# Arduino_Nano_33_IOT_Header_Schematic.net
KiCad netlist of a schematic drawn in EAGLE
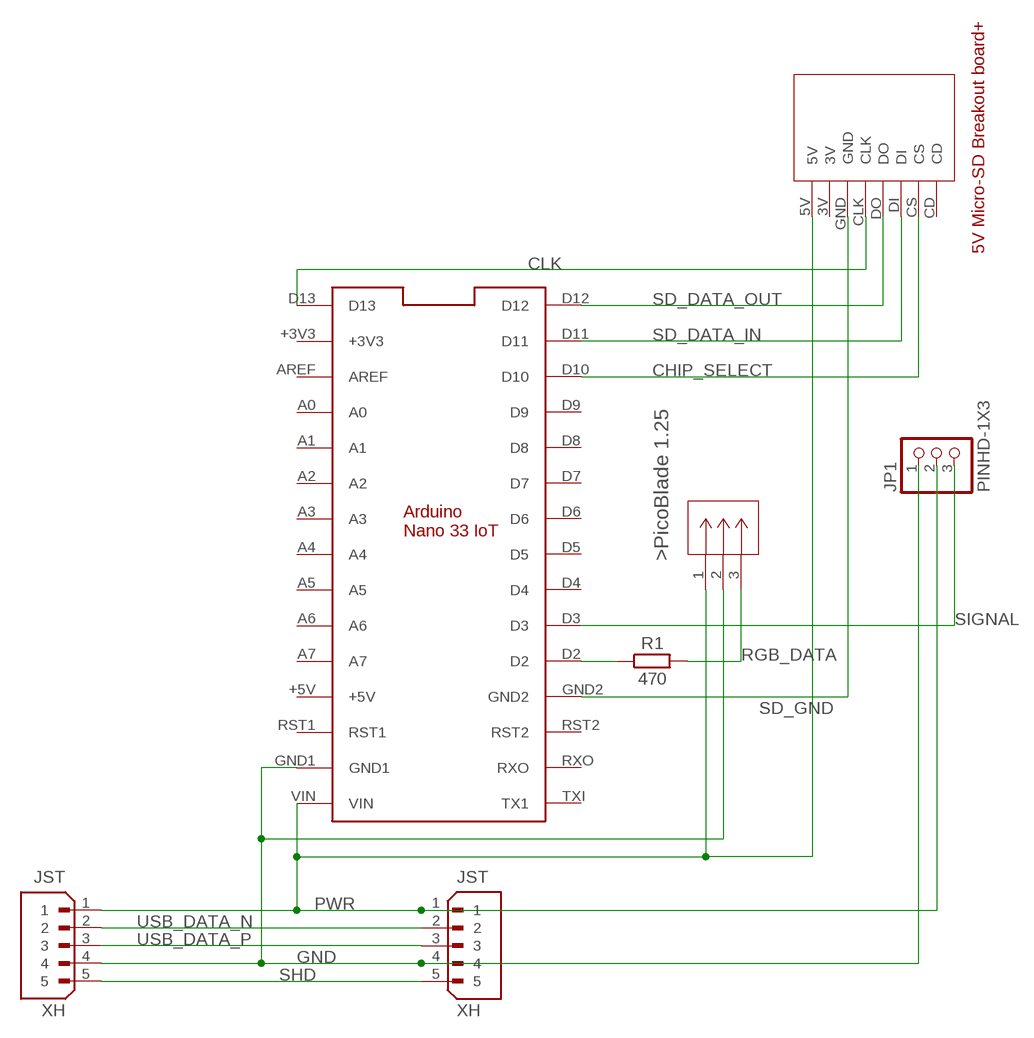
[diagram p0: schematic, sheet 1]

(export (version "E")
  (design (tool "Eeschema 10.0.6"))
  (components
    (comp (ref "HEADER2PCB")
      (value "B5B-XH-A")
      (footprint "eagle-import:JST_B5B-XH-A")
      (fields (field (name "MANUFACTURER") "JST") (field (name "MPN") "3"))
      (libsource (lib "eagle-import") (part "B5B-XH-A"))
    )
    (comp (ref "J1")
      (value "PICOBLADE_1.25_3-PINCONN03_530470310_MOL")
      (footprint "eagle-import:PICOBLADE_1.25_3-PIN")
      (fields
        (field (name "MANUFACTURER") "Molex")
        (field (name "MANUFACTURER_PART_NUMBER") "530470310")
        (field (name "COPYRIGHT") "Copyright (C) 2025 Ultra Librarian. All rights reserved.")
      )
      (libsource (lib "eagle-import") (part "PICOBLADE_1.25_3-PINCONN03_530470310_MOL"))
    )
    (comp (ref "JP1")
      (value "PINHD-1X3")
      (footprint "eagle-import:1X03")
      (libsource (lib "eagle-import") (part "PINHD-1X3"))
    )
    (comp (ref "MICROSD_HEADER")
      (value "MICROSDCARDBREAKOUTBOARD+HEADER")
      (footprint "eagle-import:5V_MICRO-SD_BREAKOUT+_HEADERS")
      (libsource (lib "eagle-import") (part "MICROSDCARDBREAKOUTBOARD+HEADER"))
    )
    (comp (ref "R1")
      (value "470")
      (footprint "eagle-import:RESAD724W46L381D178B")
      (libsource (lib "eagle-import") (part "RESISTOR_AXIAL-7.2MM-PITCH_"))
    )
    (comp (ref "U$2")
      (value "ARDUINO_NANOHEADERS")
      (footprint "eagle-import:NANO_33_IOT_HEADER")
      (libsource (lib "eagle-import") (part "ARDUINO_NANOHEADERS"))
    )
    (comp (ref "USBCONNECT")
      (value "B5B-XH-A")
      (footprint "eagle-import:JST_B5B-XH-A")
      (fields (field (name "MANUFACTURER") "JST") (field (name "MPN") "3"))
      (libsource (lib "eagle-import") (part "B5B-XH-A"))
    )
  )
  (nets
    (net (code "1") (name "/CHIP_SELECT") (class "Default")
      (node (ref "MICROSD_HEADER") (pin "CS") (pinfunction "CS_CS") (pintype "input"))
      (node (ref "U$2") (pin "D10") (pinfunction "D10_D10") (pintype "bidirectional"))
    )
    (net (code "2") (name "/CLK") (class "Default")
      (node (ref "MICROSD_HEADER") (pin "CLK") (pinfunction "CLK_CLK") (pintype "input"))
      (node (ref "U$2") (pin "D13") (pinfunction "D13_D13") (pintype "bidirectional"))
    )
    (net (code "3") (name "/GND") (class "Default")
      (node (ref "HEADER2PCB") (pin "4") (pinfunction "4_4") (pintype "passive"))
      (node (ref "J1") (pin "2") (pinfunction "2_2") (pintype "passive"))
      (node (ref "JP1") (pin "1") (pinfunction "1_1") (pintype "passive"))
      (node (ref "U$2") (pin "GND1") (pinfunction "GND1_GND1") (pintype "bidirectional"))
      (node (ref "USBCONNECT") (pin "4") (pinfunction "4_4") (pintype "passive"))
    )
    (net (code "4") (name "/PWR") (class "Default")
      (node (ref "HEADER2PCB") (pin "1") (pinfunction "1_1") (pintype "passive"))
      (node (ref "J1") (pin "1") (pinfunction "1_1") (pintype "passive"))
      (node (ref "JP1") (pin "2") (pinfunction "2_2") (pintype "passive"))
      (node (ref "MICROSD_HEADER") (pin "5V") (pinfunction "5V_5V") (pintype "input"))
      (node (ref "U$2") (pin "VIN") (pinfunction "VIN_VIN") (pintype "output"))
      (node (ref "USBCONNECT") (pin "1") (pinfunction "1_1") (pintype "passive"))
    )
    (net (code "5") (name "/RGB_DATA") (class "Default")
      (node (ref "J1") (pin "3") (pinfunction "3_3") (pintype "passive"))
      (node (ref "R1") (pin "2") (pinfunction "2_2") (pintype "passive"))
    )
    (net (code "6") (name "/SD_DATA_IN") (class "Default")
      (node (ref "MICROSD_HEADER") (pin "DI") (pinfunction "DI_DI") (pintype "input"))
      (node (ref "U$2") (pin "D11") (pinfunction "D11_D11") (pintype "bidirectional"))
    )
    (net (code "7") (name "/SD_DATA_OUT") (class "Default")
      (node (ref "MICROSD_HEADER") (pin "DO") (pinfunction "DO_DO") (pintype "output"))
      (node (ref "U$2") (pin "D12") (pinfunction "D12_D12") (pintype "bidirectional"))
    )
    (net (code "8") (name "/SD_GND") (class "Default")
      (node (ref "MICROSD_HEADER") (pin "GND") (pinfunction "GND_GND") (pintype "bidirectional"))
      (node (ref "U$2") (pin "GND2") (pinfunction "GND2_GND2") (pintype "bidirectional"))
    )
    (net (code "9") (name "/SHD") (class "Default")
      (node (ref "HEADER2PCB") (pin "5") (pinfunction "5_5") (pintype "passive"))
      (node (ref "USBCONNECT") (pin "5") (pinfunction "5_5") (pintype "passive"))
    )
    (net (code "10") (name "/SIGNAL") (class "Default")
      (node (ref "JP1") (pin "3") (pinfunction "3_3") (pintype "passive"))
      (node (ref "U$2") (pin "D3") (pinfunction "D3_D3") (pintype "bidirectional"))
    )
    (net (code "11") (name "/USB_DATA_N") (class "Default")
      (node (ref "HEADER2PCB") (pin "2") (pinfunction "2_2") (pintype "passive"))
      (node (ref "USBCONNECT") (pin "2") (pinfunction "2_2") (pintype "passive"))
    )
    (net (code "12") (name "/USB_DATA_P") (class "Default")
      (node (ref "HEADER2PCB") (pin "3") (pinfunction "3_3") (pintype "passive"))
      (node (ref "USBCONNECT") (pin "3") (pinfunction "3_3") (pintype "passive"))
    )
    (net (code "13") (name "Net-(R1-Pad1)") (class "Default")
      (node (ref "R1") (pin "1") (pinfunction "1_1") (pintype "passive"))
      (node (ref "U$2") (pin "D2") (pinfunction "D2_D2") (pintype "bidirectional"))
    )
    (net (code "14") (name "unconnected-(MICROSD_HEADER-Pad3V)") (class "Default")
      (node (ref "MICROSD_HEADER") (pin "3V") (pinfunction "3V_3V") (pintype "bidirectional"))
    )
    (net (code "15") (name "unconnected-(MICROSD_HEADER-PadCD)") (class "Default")
      (node (ref "MICROSD_HEADER") (pin "CD") (pinfunction "CD_CD") (pintype "bidirectional"))
    )
    (net (code "16") (name "unconnected-(U$2-Pad+3V3)") (class "Default")
      (node (ref "U$2") (pin "+3V3") (pinfunction "+3V3_+3V3") (pintype "input"))
    )
    (net (code "17") (name "unconnected-(U$2-Pad+5V)") (class "Default")
      (node (ref "U$2") (pin "+5V") (pinfunction "+5V_+5V") (pintype "input"))
    )
    (net (code "18") (name "unconnected-(U$2-PadA0)") (class "Default")
      (node (ref "U$2") (pin "A0") (pinfunction "A0_A0") (pintype "bidirectional"))
    )
    (net (code "19") (name "unconnected-(U$2-PadA1)") (class "Default")
      (node (ref "U$2") (pin "A1") (pinfunction "A1_A1") (pintype "bidirectional"))
    )
    (net (code "20") (name "unconnected-(U$2-PadA2)") (class "Default")
      (node (ref "U$2") (pin "A2") (pinfunction "A2_A2") (pintype "bidirectional"))
    )
    (net (code "21") (name "unconnected-(U$2-PadA3)") (class "Default")
      (node (ref "U$2") (pin "A3") (pinfunction "A3_A3") (pintype "bidirectional"))
    )
    (net (code "22") (name "unconnected-(U$2-PadA4)") (class "Default")
      (node (ref "U$2") (pin "A4") (pinfunction "A4_A4") (pintype "bidirectional"))
    )
    (net (code "23") (name "unconnected-(U$2-PadA5)") (class "Default")
      (node (ref "U$2") (pin "A5") (pinfunction "A5_A5") (pintype "bidirectional"))
    )
    (net (code "24") (name "unconnected-(U$2-PadA6)") (class "Default")
      (node (ref "U$2") (pin "A6") (pinfunction "A6_A6") (pintype "bidirectional"))
    )
    (net (code "25") (name "unconnected-(U$2-PadA7)") (class "Default")
      (node (ref "U$2") (pin "A7") (pinfunction "A7_A7") (pintype "bidirectional"))
    )
    (net (code "26") (name "unconnected-(U$2-PadAREF)") (class "Default")
      (node (ref "U$2") (pin "AREF") (pinfunction "AREF_AREF") (pintype "bidirectional"))
    )
    (net (code "27") (name "unconnected-(U$2-PadD4)") (class "Default")
      (node (ref "U$2") (pin "D4") (pinfunction "D4_D4") (pintype "bidirectional"))
    )
    (net (code "28") (name "unconnected-(U$2-PadD5)") (class "Default")
      (node (ref "U$2") (pin "D5") (pinfunction "D5_D5") (pintype "bidirectional"))
    )
    (net (code "29") (name "unconnected-(U$2-PadD6)") (class "Default")
      (node (ref "U$2") (pin "D6") (pinfunction "D6_D6") (pintype "bidirectional"))
    )
    (net (code "30") (name "unconnected-(U$2-PadD7)") (class "Default")
      (node (ref "U$2") (pin "D7") (pinfunction "D7_D7") (pintype "bidirectional"))
    )
    (net (code "31") (name "unconnected-(U$2-PadD8)") (class "Default")
      (node (ref "U$2") (pin "D8") (pinfunction "D8_D8") (pintype "bidirectional"))
    )
    (net (code "32") (name "unconnected-(U$2-PadD9)") (class "Default")
      (node (ref "U$2") (pin "D9") (pinfunction "D9_D9") (pintype "bidirectional"))
    )
    (net (code "33") (name "unconnected-(U$2-PadRST1)") (class "Default")
      (node (ref "U$2") (pin "RST1") (pinfunction "RST1_RST1") (pintype "bidirectional"))
    )
    (net (code "34") (name "unconnected-(U$2-PadRST2)") (class "Default")
      (node (ref "U$2") (pin "RST2") (pinfunction "RST2_RST2") (pintype "bidirectional"))
    )
    (net (code "35") (name "unconnected-(U$2-PadRXO)") (class "Default")
      (node (ref "U$2") (pin "RXO") (pinfunction "RXO_RXO") (pintype "input"))
    )
    (net (code "36") (name "unconnected-(U$2-TX1-PadTXI)") (class "Default")
      (node (ref "U$2") (pin "TXI") (pinfunction "TX1_TXI") (pintype "output"))
    )
  )
)
